# interfaceB-robot.net
KiCad netlist of a schematic drawn in EAGLE
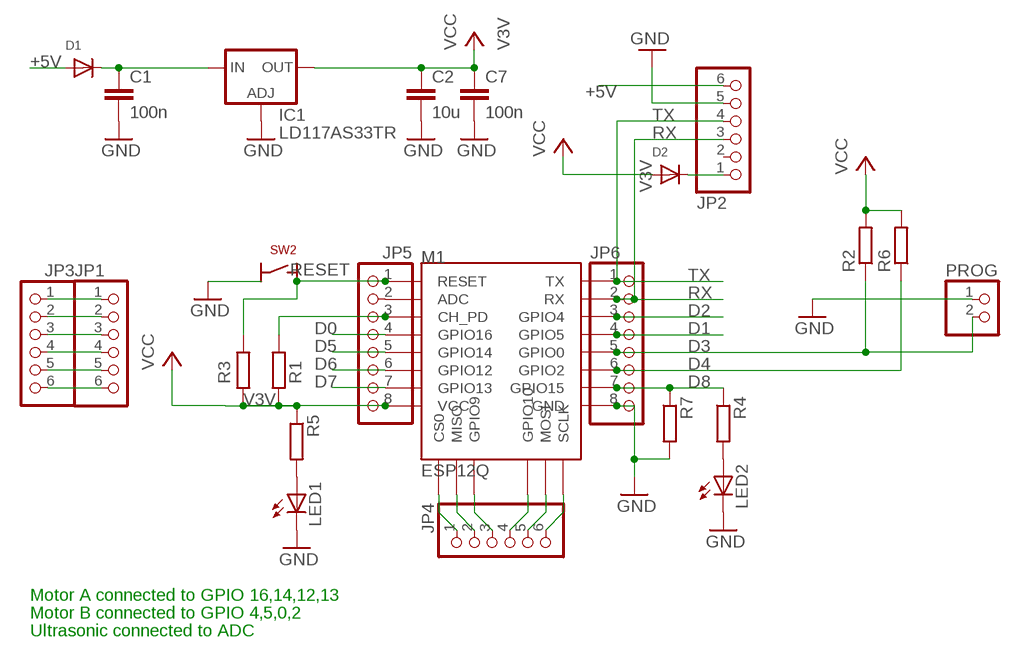
[diagram p0: schematic, sheet 1]

(export (version "E")
  (design (tool "Eeschema 10.0.6"))
  (components
    (comp (ref "C1")
      (value "100n")
      (footprint "eagle-import:C1206K")
      (libsource (lib "eagle-import") (part "C-EUC1206K"))
    )
    (comp (ref "C2")
      (value "10u")
      (footprint "eagle-import:C1206K")
      (libsource (lib "eagle-import") (part "C-EUC1206K"))
    )
    (comp (ref "C7")
      (value "100n")
      (footprint "eagle-import:C0805")
      (libsource (lib "eagle-import") (part "C-EUC0805"))
    )
    (comp (ref "D1")
      (value "DIODE_SOD-123FL")
      (footprint "eagle-import:SOD-123FL")
      (libsource (lib "eagle-import") (part "DIODE_SOD-123FL"))
    )
    (comp (ref "D2")
      (value "DIODE_SOD-123FL")
      (footprint "eagle-import:SOD-123FL")
      (libsource (lib "eagle-import") (part "DIODE_SOD-123FL"))
    )
    (comp (ref "IC1")
      (value "LD117AS33TR")
      (footprint "eagle-import:SOT223")
      (libsource (lib "eagle-import") (part "LD117A?S33TR"))
    )
    (comp (ref "JP1")
      (value "PINHD-1X6")
      (footprint "eagle-import:1X06")
      (libsource (lib "eagle-import") (part "PINHD-1X6"))
    )
    (comp (ref "JP2")
      (value "PINHD-1X6")
      (footprint "eagle-import:1X06")
      (libsource (lib "eagle-import") (part "PINHD-1X6"))
    )
    (comp (ref "JP3")
      (value "PINHD-1X6")
      (footprint "eagle-import:1X06")
      (libsource (lib "eagle-import") (part "PINHD-1X6"))
    )
    (comp (ref "JP4")
      (value "PINHD-1X6")
      (footprint "eagle-import:1X06")
      (libsource (lib "eagle-import") (part "PINHD-1X6"))
    )
    (comp (ref "JP5")
      (value "PINHD-1X8")
      (footprint "eagle-import:1X08")
      (libsource (lib "eagle-import") (part "PINHD-1X8"))
    )
    (comp (ref "JP6")
      (value "PINHD-1X8")
      (footprint "eagle-import:1X08")
      (libsource (lib "eagle-import") (part "PINHD-1X8"))
    )
    (comp (ref "LED1")
      (value "LEDCHIPLED_0805")
      (footprint "eagle-import:CHIPLED_0805")
      (libsource (lib "eagle-import") (part "LEDCHIPLED_0805"))
    )
    (comp (ref "LED2")
      (value "LEDCHIPLED_0805")
      (footprint "eagle-import:CHIPLED_0805")
      (libsource (lib "eagle-import") (part "LEDCHIPLED_0805"))
    )
    (comp (ref "M1")
      (value "ESP12Q")
      (footprint "eagle-import:ESP12Q")
      (libsource (lib "eagle-import") (part "ESP12Q"))
    )
    (comp (ref "PROG")
      (value "PINHD-1X2")
      (footprint "eagle-import:1X02")
      (libsource (lib "eagle-import") (part "PINHD-1X2"))
    )
    (comp (ref "R1")
      (value "R-EU_R1206")
      (footprint "eagle-import:R1206")
      (libsource (lib "eagle-import") (part "R-EU_R1206"))
    )
    (comp (ref "R2")
      (value "R-EU_R0805")
      (footprint "eagle-import:R0805")
      (libsource (lib "eagle-import") (part "R-EU_R0805"))
    )
    (comp (ref "R3")
      (value "R-EU_R1206")
      (footprint "eagle-import:R1206")
      (libsource (lib "eagle-import") (part "R-EU_R1206"))
    )
    (comp (ref "R4")
      (value "R-EU_R0805")
      (footprint "eagle-import:R0805")
      (libsource (lib "eagle-import") (part "R-EU_R0805"))
    )
    (comp (ref "R5")
      (value "R-EU_R0805")
      (footprint "eagle-import:R0805")
      (libsource (lib "eagle-import") (part "R-EU_R0805"))
    )
    (comp (ref "R6")
      (value "R-EU_R0805")
      (footprint "eagle-import:R0805")
      (libsource (lib "eagle-import") (part "R-EU_R0805"))
    )
    (comp (ref "R7")
      (value "R-EU_R0805")
      (footprint "eagle-import:R0805")
      (libsource (lib "eagle-import") (part "R-EU_R0805"))
    )
    (comp (ref "SW2")
      (value "SW4")
      (footprint "eagle-import:SW45-65")
      (libsource (lib "eagle-import") (part "SW4"))
    )
  )
  (nets
    (net (code "1") (name "/+5V") (class "Default")
      (node (ref "D1") (pin "A") (pinfunction "A_A") (pintype "passive"))
      (node (ref "JP2") (pin "6") (pinfunction "6_6") (pintype "passive"))
    )
    (net (code "2") (name "/D0") (class "Default")
      (node (ref "JP5") (pin "4") (pinfunction "4_4") (pintype "passive"))
      (node (ref "M1") (pin "GPIO16") (pinfunction "GPIO16_GPIO16") (pintype "bidirectional"))
    )
    (net (code "3") (name "/D1") (class "Default")
      (node (ref "JP6") (pin "4") (pinfunction "4_4") (pintype "passive"))
      (node (ref "M1") (pin "GPIO5") (pinfunction "GPIO5_GPIO5") (pintype "bidirectional"))
    )
    (net (code "4") (name "/D2") (class "Default")
      (node (ref "JP6") (pin "3") (pinfunction "3_3") (pintype "passive"))
      (node (ref "M1") (pin "GPIO4") (pinfunction "GPIO4_GPIO4") (pintype "bidirectional"))
    )
    (net (code "5") (name "/D3") (class "Default")
      (node (ref "JP6") (pin "5") (pinfunction "5_5") (pintype "passive"))
      (node (ref "M1") (pin "GPIO0") (pinfunction "GPIO0_GPIO0") (pintype "bidirectional"))
      (node (ref "PROG") (pin "2") (pinfunction "2_2") (pintype "passive"))
      (node (ref "R2") (pin "1") (pinfunction "1_1") (pintype "passive"))
    )
    (net (code "6") (name "/D4") (class "Default")
      (node (ref "JP6") (pin "6") (pinfunction "6_6") (pintype "passive"))
      (node (ref "M1") (pin "GPIO2") (pinfunction "GPIO2_GPIO2") (pintype "bidirectional"))
      (node (ref "R6") (pin "1") (pinfunction "1_1") (pintype "passive"))
    )
    (net (code "7") (name "/D5") (class "Default")
      (node (ref "JP5") (pin "5") (pinfunction "5_5") (pintype "passive"))
      (node (ref "M1") (pin "GPIO14") (pinfunction "GPIO14_GPIO14") (pintype "bidirectional"))
    )
    (net (code "8") (name "/D6") (class "Default")
      (node (ref "JP5") (pin "6") (pinfunction "6_6") (pintype "passive"))
      (node (ref "M1") (pin "GPIO12") (pinfunction "GPIO12_GPIO12") (pintype "bidirectional"))
    )
    (net (code "9") (name "/D7") (class "Default")
      (node (ref "JP5") (pin "7") (pinfunction "7_7") (pintype "passive"))
      (node (ref "M1") (pin "GPIO13") (pinfunction "GPIO13_GPIO13") (pintype "bidirectional"))
    )
    (net (code "10") (name "/D8") (class "Default")
      (node (ref "JP6") (pin "7") (pinfunction "7_7") (pintype "passive"))
      (node (ref "M1") (pin "GPIO15") (pinfunction "GPIO15_GPIO15") (pintype "bidirectional"))
      (node (ref "R4") (pin "1") (pinfunction "1_1") (pintype "passive"))
      (node (ref "R7") (pin "1") (pinfunction "1_1") (pintype "passive"))
    )
    (net (code "11") (name "/RESET") (class "Default")
      (node (ref "JP5") (pin "1") (pinfunction "1_1") (pintype "passive"))
      (node (ref "M1") (pin "RESET") (pinfunction "RESET_RESET") (pintype "bidirectional"))
      (node (ref "R3") (pin "1") (pinfunction "1_1") (pintype "passive"))
      (node (ref "SW2") (pin "2") (pinfunction "S_2") (pintype "bidirectional"))
    )
    (net (code "12") (name "/RX") (class "Default")
      (node (ref "JP2") (pin "3") (pinfunction "3_3") (pintype "passive"))
      (node (ref "JP6") (pin "2") (pinfunction "2_2") (pintype "passive"))
      (node (ref "M1") (pin "RX") (pinfunction "RX_RX") (pintype "bidirectional"))
    )
    (net (code "13") (name "/TX") (class "Default")
      (node (ref "JP2") (pin "4") (pinfunction "4_4") (pintype "passive"))
      (node (ref "JP6") (pin "1") (pinfunction "1_1") (pintype "passive"))
      (node (ref "M1") (pin "TX") (pinfunction "TX_TX") (pintype "bidirectional"))
    )
    (net (code "14") (name "GND") (class "Default")
      (node (ref "C1") (pin "2") (pinfunction "2_2") (pintype "passive"))
      (node (ref "C2") (pin "2") (pinfunction "2_2") (pintype "passive"))
      (node (ref "C7") (pin "2") (pinfunction "2_2") (pintype "passive"))
      (node (ref "IC1") (pin "1") (pinfunction "ADJ_1") (pintype "input"))
      (node (ref "JP2") (pin "5") (pinfunction "5_5") (pintype "passive"))
      (node (ref "JP6") (pin "8") (pinfunction "8_8") (pintype "passive"))
      (node (ref "LED1") (pin "C") (pinfunction "C_C") (pintype "passive"))
      (node (ref "LED2") (pin "C") (pinfunction "C_C") (pintype "passive"))
      (node (ref "M1") (pin "GND") (pinfunction "GND_GND") (pintype "bidirectional"))
      (node (ref "PROG") (pin "1") (pinfunction "1_1") (pintype "passive"))
      (node (ref "R7") (pin "2") (pinfunction "2_2") (pintype "passive"))
      (node (ref "SW2") (pin "4") (pinfunction "P_4") (pintype "bidirectional"))
    )
    (net (code "15") (name "Net-(D2-PadC)") (class "Default")
      (node (ref "D2") (pin "C") (pinfunction "C_C") (pintype "passive"))
      (node (ref "JP2") (pin "1") (pinfunction "1_1") (pintype "passive"))
    )
    (net (code "16") (name "Net-(IC1-IN)") (class "Default")
      (node (ref "C1") (pin "1") (pinfunction "1_1") (pintype "passive"))
      (node (ref "D1") (pin "C") (pinfunction "C_C") (pintype "passive"))
      (node (ref "IC1") (pin "3") (pinfunction "IN_3") (pintype "input"))
    )
    (net (code "17") (name "Net-(JP1-Pad1)") (class "Default")
      (node (ref "JP1") (pin "1") (pinfunction "1_1") (pintype "passive"))
      (node (ref "JP3") (pin "1") (pinfunction "1_1") (pintype "passive"))
    )
    (net (code "18") (name "Net-(JP1-Pad2)") (class "Default")
      (node (ref "JP1") (pin "2") (pinfunction "2_2") (pintype "passive"))
      (node (ref "JP3") (pin "2") (pinfunction "2_2") (pintype "passive"))
    )
    (net (code "19") (name "Net-(JP1-Pad3)") (class "Default")
      (node (ref "JP1") (pin "3") (pinfunction "3_3") (pintype "passive"))
      (node (ref "JP3") (pin "3") (pinfunction "3_3") (pintype "passive"))
    )
    (net (code "20") (name "Net-(JP1-Pad4)") (class "Default")
      (node (ref "JP1") (pin "4") (pinfunction "4_4") (pintype "passive"))
      (node (ref "JP3") (pin "4") (pinfunction "4_4") (pintype "passive"))
    )
    (net (code "21") (name "Net-(JP1-Pad5)") (class "Default")
      (node (ref "JP1") (pin "5") (pinfunction "5_5") (pintype "passive"))
      (node (ref "JP3") (pin "5") (pinfunction "5_5") (pintype "passive"))
    )
    (net (code "22") (name "Net-(JP1-Pad6)") (class "Default")
      (node (ref "JP1") (pin "6") (pinfunction "6_6") (pintype "passive"))
      (node (ref "JP3") (pin "6") (pinfunction "6_6") (pintype "passive"))
    )
    (net (code "23") (name "Net-(JP4-Pad1)") (class "Default")
      (node (ref "JP4") (pin "1") (pinfunction "1_1") (pintype "passive"))
      (node (ref "M1") (pin "CS0") (pinfunction "CS0_CS0") (pintype "bidirectional"))
    )
    (net (code "24") (name "Net-(JP4-Pad2)") (class "Default")
      (node (ref "JP4") (pin "2") (pinfunction "2_2") (pintype "passive"))
      (node (ref "M1") (pin "MISO") (pinfunction "MISO_MISO") (pintype "bidirectional"))
    )
    (net (code "25") (name "Net-(JP4-Pad3)") (class "Default")
      (node (ref "JP4") (pin "3") (pinfunction "3_3") (pintype "passive"))
      (node (ref "M1") (pin "GPIO9") (pinfunction "GPIO9_GPIO9") (pintype "bidirectional"))
    )
    (net (code "26") (name "Net-(JP4-Pad4)") (class "Default")
      (node (ref "JP4") (pin "4") (pinfunction "4_4") (pintype "passive"))
      (node (ref "M1") (pin "GPIO10") (pinfunction "GPIO10_GPIO10") (pintype "bidirectional"))
    )
    (net (code "27") (name "Net-(JP4-Pad5)") (class "Default")
      (node (ref "JP4") (pin "5") (pinfunction "5_5") (pintype "passive"))
      (node (ref "M1") (pin "MOSI") (pinfunction "MOSI_MOSI") (pintype "bidirectional"))
    )
    (net (code "28") (name "Net-(JP4-Pad6)") (class "Default")
      (node (ref "JP4") (pin "6") (pinfunction "6_6") (pintype "passive"))
      (node (ref "M1") (pin "SCLK") (pinfunction "SCLK_SCLK") (pintype "bidirectional"))
    )
    (net (code "29") (name "Net-(JP5-Pad2)") (class "Default")
      (node (ref "JP5") (pin "2") (pinfunction "2_2") (pintype "passive"))
      (node (ref "M1") (pin "ADC") (pinfunction "ADC_ADC") (pintype "bidirectional"))
    )
    (net (code "30") (name "Net-(JP5-Pad3)") (class "Default")
      (node (ref "JP5") (pin "3") (pinfunction "3_3") (pintype "passive"))
      (node (ref "M1") (pin "CH_PD") (pinfunction "CH_PD_CH_PD") (pintype "bidirectional"))
      (node (ref "R1") (pin "1") (pinfunction "1_1") (pintype "passive"))
    )
    (net (code "31") (name "Net-(LED1-PadA)") (class "Default")
      (node (ref "LED1") (pin "A") (pinfunction "A_A") (pintype "passive"))
      (node (ref "R5") (pin "2") (pinfunction "2_2") (pintype "passive"))
    )
    (net (code "32") (name "Net-(LED2-PadA)") (class "Default")
      (node (ref "LED2") (pin "A") (pinfunction "A_A") (pintype "passive"))
      (node (ref "R4") (pin "2") (pinfunction "2_2") (pintype "passive"))
    )
    (net (code "33") (name "VCC") (class "Default")
      (node (ref "C2") (pin "1") (pinfunction "1_1") (pintype "passive"))
      (node (ref "C7") (pin "1") (pinfunction "1_1") (pintype "passive"))
      (node (ref "D2") (pin "A") (pinfunction "A_A") (pintype "passive"))
      (node (ref "IC1") (pin "4") (pinfunction "OUT_4") (pintype "passive"))
      (node (ref "JP5") (pin "8") (pinfunction "8_8") (pintype "passive"))
      (node (ref "M1") (pin "VCC") (pinfunction "VCC_VCC") (pintype "bidirectional"))
      (node (ref "R1") (pin "2") (pinfunction "2_2") (pintype "passive"))
      (node (ref "R2") (pin "2") (pinfunction "2_2") (pintype "passive"))
      (node (ref "R3") (pin "2") (pinfunction "2_2") (pintype "passive"))
      (node (ref "R5") (pin "1") (pinfunction "1_1") (pintype "passive"))
      (node (ref "R6") (pin "2") (pinfunction "2_2") (pintype "passive"))
    )
    (net (code "34") (name "unconnected-(JP2-Pad2)") (class "Default")
      (node (ref "JP2") (pin "2") (pinfunction "2_2") (pintype "passive"))
    )
    (net (code "35") (name "unconnected-(SW2-P-Pad3)") (class "Default")
      (node (ref "SW2") (pin "3") (pinfunction "P_3") (pintype "bidirectional"))
    )
    (net (code "36") (name "unconnected-(SW2-S-Pad1)") (class "Default")
      (node (ref "SW2") (pin "1") (pinfunction "S_1") (pintype "bidirectional"))
    )
  )
)
